# Heart.net
KiCad netlist of a schematic drawn in EAGLE
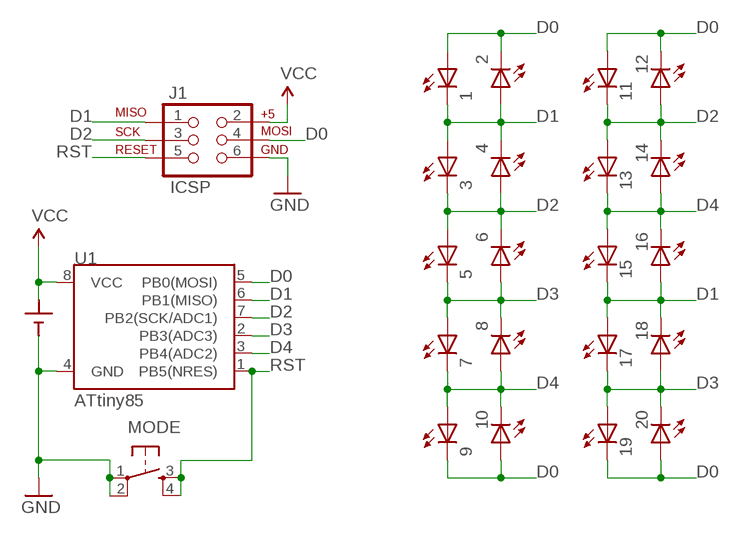
[diagram p0: schematic, sheet 1]

(export (version "E")
  (design (tool "Eeschema 10.0.6"))
  (components
    (comp (ref "1")
      (value "LED5MM")
      (footprint "eagle-import:LED5MM")
      (libsource (lib "eagle-import") (part "LED5MM"))
    )
    (comp (ref "2")
      (value "LED5MM")
      (footprint "eagle-import:LED5MM")
      (libsource (lib "eagle-import") (part "LED5MM"))
    )
    (comp (ref "3")
      (value "LED5MM")
      (footprint "eagle-import:LED5MM")
      (libsource (lib "eagle-import") (part "LED5MM"))
    )
    (comp (ref "4")
      (value "LED5MM")
      (footprint "eagle-import:LED5MM")
      (libsource (lib "eagle-import") (part "LED5MM"))
    )
    (comp (ref "5")
      (value "LED5MM")
      (footprint "eagle-import:LED5MM")
      (libsource (lib "eagle-import") (part "LED5MM"))
    )
    (comp (ref "6")
      (value "LED5MM")
      (footprint "eagle-import:LED5MM")
      (libsource (lib "eagle-import") (part "LED5MM"))
    )
    (comp (ref "7")
      (value "LED5MM")
      (footprint "eagle-import:LED5MM")
      (libsource (lib "eagle-import") (part "LED5MM"))
    )
    (comp (ref "8")
      (value "LED5MM")
      (footprint "eagle-import:LED5MM")
      (libsource (lib "eagle-import") (part "LED5MM"))
    )
    (comp (ref "9")
      (value "LED5MM")
      (footprint "eagle-import:LED5MM")
      (libsource (lib "eagle-import") (part "LED5MM"))
    )
    (comp (ref "10")
      (value "LED5MM")
      (footprint "eagle-import:LED5MM")
      (libsource (lib "eagle-import") (part "LED5MM"))
    )
    (comp (ref "11")
      (value "LED5MM")
      (footprint "eagle-import:LED5MM")
      (libsource (lib "eagle-import") (part "LED5MM"))
    )
    (comp (ref "12")
      (value "LED5MM")
      (footprint "eagle-import:LED5MM")
      (libsource (lib "eagle-import") (part "LED5MM"))
    )
    (comp (ref "13")
      (value "LED5MM")
      (footprint "eagle-import:LED5MM")
      (libsource (lib "eagle-import") (part "LED5MM"))
    )
    (comp (ref "14")
      (value "LED5MM")
      (footprint "eagle-import:LED5MM")
      (libsource (lib "eagle-import") (part "LED5MM"))
    )
    (comp (ref "15")
      (value "LED5MM")
      (footprint "eagle-import:LED5MM")
      (libsource (lib "eagle-import") (part "LED5MM"))
    )
    (comp (ref "16")
      (value "LED5MM")
      (footprint "eagle-import:LED5MM")
      (libsource (lib "eagle-import") (part "LED5MM"))
    )
    (comp (ref "17")
      (value "LED5MM")
      (footprint "eagle-import:LED5MM")
      (libsource (lib "eagle-import") (part "LED5MM"))
    )
    (comp (ref "18")
      (value "LED5MM")
      (footprint "eagle-import:LED5MM")
      (libsource (lib "eagle-import") (part "LED5MM"))
    )
    (comp (ref "19")
      (value "LED5MM")
      (footprint "eagle-import:LED5MM")
      (libsource (lib "eagle-import") (part "LED5MM"))
    )
    (comp (ref "20")
      (value "LED5MM")
      (footprint "eagle-import:LED5MM")
      (libsource (lib "eagle-import") (part "LED5MM"))
    )
    (comp (ref "BATT")
      (value "CR2032")
      (footprint "eagle-import:CR2032-THRU")
      (libsource (lib "eagle-import") (part "BATTCR2032_THRU"))
    )
    (comp (ref "J1")
      (value "ICSP")
      (footprint "eagle-import:2X3-NS")
      (libsource (lib "eagle-import") (part "AVR_SPI_PRG_6LABELED"))
    )
    (comp (ref "MODE")
      (value "TAC_SWITCHPTH")
      (footprint "eagle-import:TACTILE-PTH")
      (libsource (lib "eagle-import") (part "TAC_SWITCHPTH"))
    )
    (comp (ref "U1")
      (value "ATtiny85")
      (footprint "eagle-import:DIP08")
      (libsource (lib "eagle-import") (part "ATTINY45TINY85-20-DIP"))
    )
  )
  (nets
    (net (code "1") (name "/D0") (class "Default")
      (node (ref "1") (pin "A") (pinfunction "A_A") (pintype "passive"))
      (node (ref "10") (pin "A") (pinfunction "A_A") (pintype "passive"))
      (node (ref "11") (pin "A") (pinfunction "A_A") (pintype "passive"))
      (node (ref "12") (pin "K") (pinfunction "C_K") (pintype "passive"))
      (node (ref "19") (pin "K") (pinfunction "C_K") (pintype "passive"))
      (node (ref "2") (pin "K") (pinfunction "C_K") (pintype "passive"))
      (node (ref "20") (pin "A") (pinfunction "A_A") (pintype "passive"))
      (node (ref "9") (pin "K") (pinfunction "C_K") (pintype "passive"))
      (node (ref "J1") (pin "4") (pinfunction "MOSI_4") (pintype "passive"))
      (node (ref "U1") (pin "5") (pinfunction "PB0(MOSI)_5") (pintype "bidirectional"))
    )
    (net (code "2") (name "/D1") (class "Default")
      (node (ref "1") (pin "K") (pinfunction "C_K") (pintype "passive"))
      (node (ref "15") (pin "K") (pinfunction "C_K") (pintype "passive"))
      (node (ref "16") (pin "A") (pinfunction "A_A") (pintype "passive"))
      (node (ref "17") (pin "A") (pinfunction "A_A") (pintype "passive"))
      (node (ref "18") (pin "K") (pinfunction "C_K") (pintype "passive"))
      (node (ref "2") (pin "A") (pinfunction "A_A") (pintype "passive"))
      (node (ref "3") (pin "A") (pinfunction "A_A") (pintype "passive"))
      (node (ref "4") (pin "K") (pinfunction "C_K") (pintype "passive"))
      (node (ref "J1") (pin "1") (pinfunction "MISO_1") (pintype "passive"))
      (node (ref "U1") (pin "6") (pinfunction "PB1(MISO)_6") (pintype "bidirectional"))
    )
    (net (code "3") (name "/D2") (class "Default")
      (node (ref "11") (pin "K") (pinfunction "C_K") (pintype "passive"))
      (node (ref "12") (pin "A") (pinfunction "A_A") (pintype "passive"))
      (node (ref "13") (pin "A") (pinfunction "A_A") (pintype "passive"))
      (node (ref "14") (pin "K") (pinfunction "C_K") (pintype "passive"))
      (node (ref "3") (pin "K") (pinfunction "C_K") (pintype "passive"))
      (node (ref "4") (pin "A") (pinfunction "A_A") (pintype "passive"))
      (node (ref "5") (pin "A") (pinfunction "A_A") (pintype "passive"))
      (node (ref "6") (pin "K") (pinfunction "C_K") (pintype "passive"))
      (node (ref "J1") (pin "3") (pinfunction "SCK_3") (pintype "passive"))
      (node (ref "U1") (pin "7") (pinfunction "PB2(SCK/ADC1)_7") (pintype "bidirectional"))
    )
    (net (code "4") (name "/D3") (class "Default")
      (node (ref "17") (pin "K") (pinfunction "C_K") (pintype "passive"))
      (node (ref "18") (pin "A") (pinfunction "A_A") (pintype "passive"))
      (node (ref "19") (pin "A") (pinfunction "A_A") (pintype "passive"))
      (node (ref "20") (pin "K") (pinfunction "C_K") (pintype "passive"))
      (node (ref "5") (pin "K") (pinfunction "C_K") (pintype "passive"))
      (node (ref "6") (pin "A") (pinfunction "A_A") (pintype "passive"))
      (node (ref "7") (pin "A") (pinfunction "A_A") (pintype "passive"))
      (node (ref "8") (pin "K") (pinfunction "C_K") (pintype "passive"))
      (node (ref "U1") (pin "2") (pinfunction "PB3(ADC3)_2") (pintype "bidirectional"))
    )
    (net (code "5") (name "/D4") (class "Default")
      (node (ref "10") (pin "K") (pinfunction "C_K") (pintype "passive"))
      (node (ref "13") (pin "K") (pinfunction "C_K") (pintype "passive"))
      (node (ref "14") (pin "A") (pinfunction "A_A") (pintype "passive"))
      (node (ref "15") (pin "A") (pinfunction "A_A") (pintype "passive"))
      (node (ref "16") (pin "K") (pinfunction "C_K") (pintype "passive"))
      (node (ref "7") (pin "K") (pinfunction "C_K") (pintype "passive"))
      (node (ref "8") (pin "A") (pinfunction "A_A") (pintype "passive"))
      (node (ref "9") (pin "A") (pinfunction "A_A") (pintype "passive"))
      (node (ref "U1") (pin "3") (pinfunction "PB4(ADC2)_3") (pintype "bidirectional"))
    )
    (net (code "6") (name "/RST") (class "Default")
      (node (ref "J1") (pin "5") (pinfunction "RST_5") (pintype "passive"))
      (node (ref "MODE") (pin "3") (pinfunction "3_3") (pintype "passive"))
      (node (ref "MODE") (pin "4") (pinfunction "4_4") (pintype "passive"))
      (node (ref "U1") (pin "1") (pinfunction "PB5(NRES)_1") (pintype "bidirectional"))
    )
    (net (code "7") (name "GND") (class "Default")
      (node (ref "BATT") (pin "-") (pinfunction "-_-") (pintype "power_in"))
      (node (ref "J1") (pin "6") (pinfunction "GND_6") (pintype "passive"))
      (node (ref "MODE") (pin "1") (pinfunction "1_1") (pintype "passive"))
      (node (ref "MODE") (pin "2") (pinfunction "2_2") (pintype "passive"))
      (node (ref "U1") (pin "4") (pinfunction "GND_4") (pintype "bidirectional"))
    )
    (net (code "8") (name "VCC") (class "Default")
      (node (ref "BATT") (pin "+1") (pinfunction "+_+1") (pintype "power_in"))
      (node (ref "J1") (pin "2") (pinfunction "V+_2") (pintype "passive"))
      (node (ref "U1") (pin "8") (pinfunction "VCC_8") (pintype "bidirectional"))
    )
  )
)
